# Power-Sheet-1.net
KiCad netlist of a schematic drawn in Altium Designer
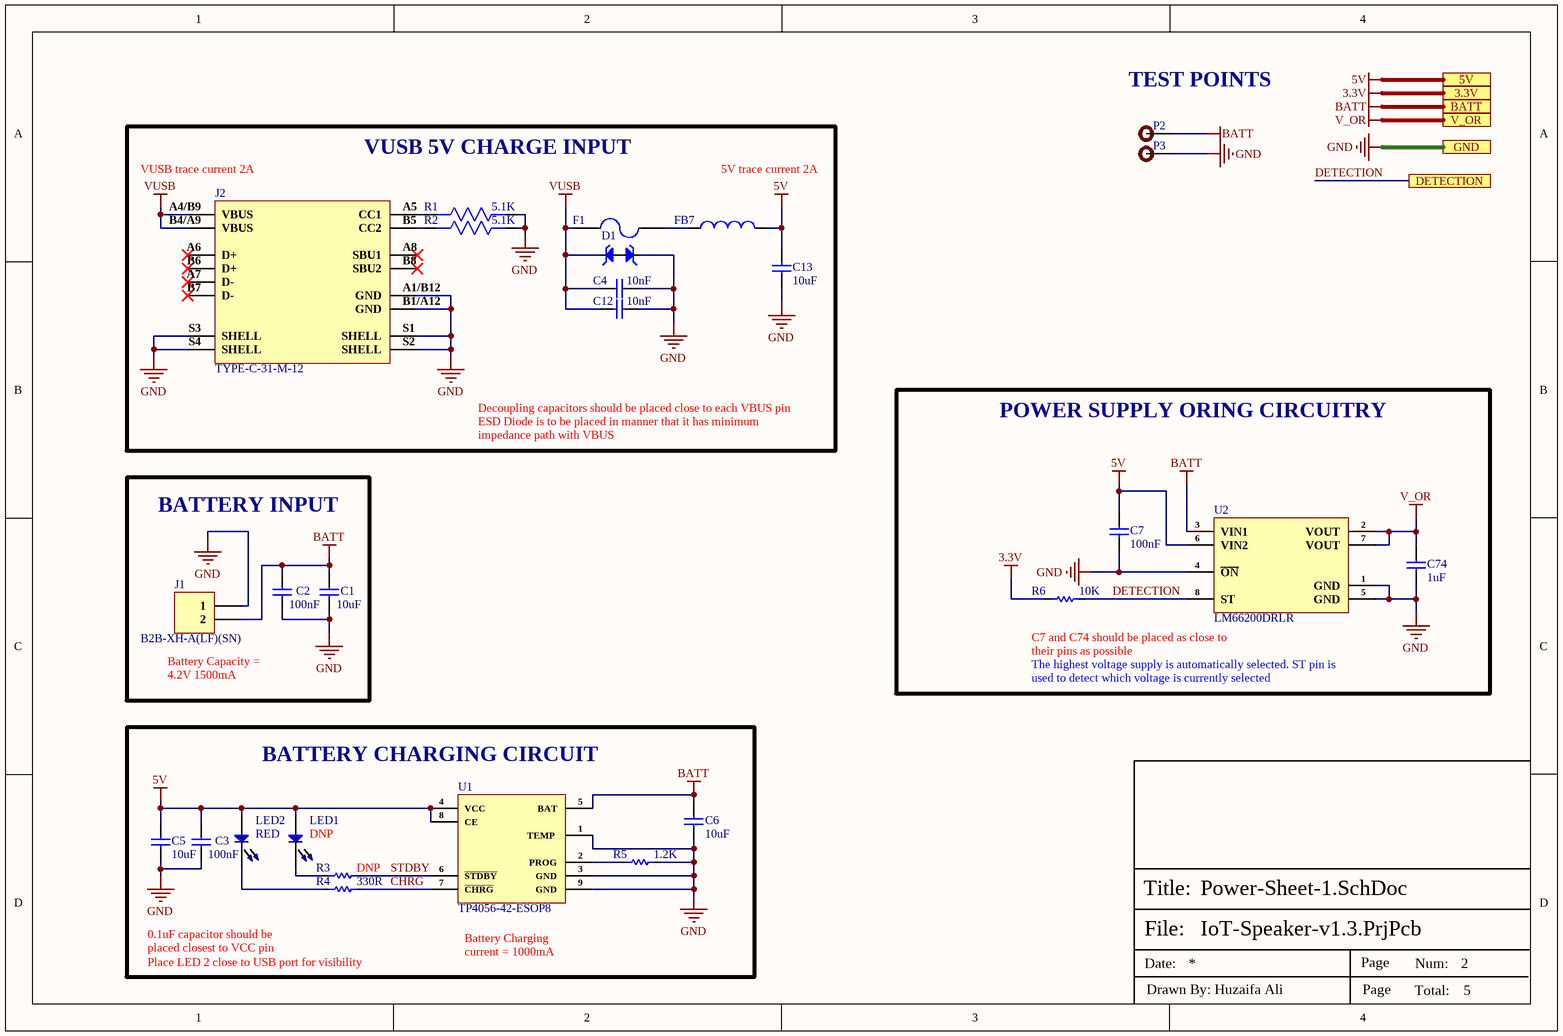
[diagram p0: Power-Sheet-1.SchDoc]

(export (version "E")
  (design (tool "Eeschema 10.0.6"))
  (components
    (comp (ref "C1")
      (value "10uF")
      (footprint "Cap-0805")
      (description "CAP CER 10UF 25V X5R 0805")
      (fields
        (field (name "MANUFACTURER") "Yageo")
        (field (name "MANUFACTURER PART NUMBER") "CC0805KKX5R8BB106")
      )
      (libsource (lib "eSpark_centralized_Library(2022)") (part "CC0805KKX5R8BB106"))
    )
    (comp (ref "C2")
      (value "100nF")
      (footprint "Cap-0402")
      (description "CAP CER 0.1UF 25V X5R 0402")
      (fields
        (field (name "MANUFACTURER") "Yageo")
        (field (name "MANUFACTURER PART NUMBER") "CC0402KRX5R8BB104")
      )
      (libsource (lib "eSpark_centralized_Library(2022)") (part "CC0402KRX5R8BB104"))
    )
    (comp (ref "C3")
      (value "100nF")
      (footprint "Cap-0402")
      (description "CAP CER 0.1UF 25V X5R 0402")
      (fields
        (field (name "MANUFACTURER") "Yageo")
        (field (name "MANUFACTURER PART NUMBER") "CC0402KRX5R8BB104")
      )
      (libsource (lib "eSpark_centralized_Library(2022)") (part "CC0402KRX5R8BB104"))
    )
    (comp (ref "C4")
      (value "10nF")
      (footprint "Cap-0603")
      (description "CAP CER 10000PF 50V C0G/NPO 0603")
      (fields
        (field (name "MANUFACTURER") "Yageo")
        (field (name "MANUFACTURER PART NUMBER") "CC0603JRNPO9BN103")
      )
      (libsource (lib "eSpark_centralized_Library(2022)") (part "CC0603JRNPO9BN103"))
    )
    (comp (ref "C5")
      (value "10uF")
      (footprint "Cap-0805")
      (description "CAP CER 10UF 25V X5R 0805")
      (fields
        (field (name "MANUFACTURER") "Yageo")
        (field (name "MANUFACTURER PART NUMBER") "CC0805KKX5R8BB106")
      )
      (libsource (lib "eSpark_centralized_Library(2022)") (part "CC0805KKX5R8BB106"))
    )
    (comp (ref "C6")
      (value "10uF")
      (footprint "Cap-0805")
      (description "CAP CER 10UF 25V X5R 0805")
      (fields
        (field (name "MANUFACTURER") "Yageo")
        (field (name "MANUFACTURER PART NUMBER") "CC0805KKX5R8BB106")
      )
      (libsource (lib "eSpark_centralized_Library(2022)") (part "CC0805KKX5R8BB106"))
    )
    (comp (ref "C7")
      (value "100nF")
      (footprint "Cap-0402")
      (description "CAP CER 0.1UF 25V X5R 0402")
      (fields
        (field (name "MANUFACTURER") "Yageo")
        (field (name "MANUFACTURER PART NUMBER") "CC0402KRX5R8BB104")
      )
      (libsource (lib "eSpark_centralized_Library(2022)") (part "CC0402KRX5R8BB104"))
    )
    (comp (ref "C12")
      (value "10nF")
      (footprint "Cap-0603")
      (description "CAP CER 10000PF 50V C0G/NPO 0603")
      (fields
        (field (name "MANUFACTURER") "Yageo")
        (field (name "MANUFACTURER PART NUMBER") "CC0603JRNPO9BN103")
      )
      (libsource (lib "eSpark_centralized_Library(2022)") (part "CC0603JRNPO9BN103"))
    )
    (comp (ref "C13")
      (value "10uF")
      (footprint "Cap-0805")
      (description "CAP CER 10UF 25V X5R 0805")
      (fields
        (field (name "MANUFACTURER") "Yageo")
        (field (name "MANUFACTURER PART NUMBER") "CC0805KKX5R8BB106")
      )
      (libsource (lib "eSpark_centralized_Library(2022)") (part "CC0805KKX5R8BB106"))
    )
    (comp (ref "C74")
      (value "1uF")
      (footprint "Cap-0603")
      (description "CAP CER 1UF 25V X5R 0603")
      (fields
        (field (name "MANUFACTURER") "Yageo")
        (field (name "MANUFACTURER PART NUMBER") "CC0603KRX5R8BB105")
      )
      (libsource (lib "eSpark_centralized_Library(2022)") (part "CC0603KRX5R8BB105"))
    )
    (comp (ref "D1")
      (value "PESD5V0H1BSFYL")
      (footprint "DSN0603-2")
      (description "TVS DIODE 5VWM 6.3VC DSN0603-2")
      (fields (field (name "MANUFACTURER") "Nexperia") (field (name "LCSC PART NUMBER") "C477989"))
      (libsource (lib "eSpark Libraries") (part "PESD5V0H1BSFYL"))
    )
    (comp (ref "F1")
      (value "BSMD0805L-200")
      (footprint "Fuse-0805")
      (description "6V 2A 50A 1W -40℃~+85℃ 4A 4mΩ 5s 45mΩ 0805 Resettable Fuses ROHS")
      (fields (field (name "MANUFACTURER") "BHFUSE") (field (name "LCSC PART NUMBER") "C2757931"))
      (libsource (lib "eSpark_centralized_Library(2022)") (part "BSMD0805L-200"))
    )
    (comp (ref "FB7")
      (value "100MHz")
      (footprint "IND-1206")
      (description "FERRITE BEAD 120 OHM 1206 1LN")
      (fields
        (field (name "MANUFACTURER") "Murata")
        (field (name "MANUFACTURER PART NUMBER") "BLM31PG121SN1L")
      )
      (libsource (lib "eSpark_centralized_Library(2022)") (part "BLM31PG121SN1L"))
    )
    (comp (ref "J1")
      (value "B2B-XH-A(LF)(SN)")
      (footprint "B2B-XH-A(LF)(SN)_")
      (description "Conn Shrouded Header (4 Sides) HDR 2 POS 2.5mm Solder ST Thru-Hole Box")
      (fields (field (name "MANUFACTURER") "JST") (field (name "LCSC PART NUMBER") "C158012"))
      (libsource (lib "eSpark_centralized_Library(2022)") (part "B2B-XH-A(LF)(SN)"))
    )
    (comp (ref "J2")
      (value "TYPE-C-31-M-12")
      (footprint "TYPE-C-31-M-12_")
      (description "250mA 1 16 Female Type-C SMD USB Connectors ROHS")
      (fields
        (field (name "MANUFACTURER") "Korean Hroparts Elec")
        (field (name "LCSC PART NUMBER") "C165948")
      )
      (libsource (lib "eSpark_centralized_Library(2022)") (part "TYPE-C-31-M-12"))
    )
    (comp (ref "LED1")
      (value "DNP")
      (footprint "LED-0603")
      (description "Emerald 0603 Light Emitting Diodes (LED) ROHS")
      (fields
        (field (name "MANUFACTURER") "Foshan NationStar Optoelectronics")
        (field (name "MANUFACTURER PART NUMBER") "NCD0603G2")
      )
      (libsource (lib "eSpark_centralized_Library(2022)") (part "NCD0603G2"))
    )
    (comp (ref "LED2")
      (value "RED")
      (footprint "LED-0603")
      (description "0603 Light Emitting Diodes (LED) ROHS")
      (fields
        (field (name "MANUFACTURER") "Foshan NationStar Optoelectronics")
        (field (name "MANUFACTURER PART NUMBER") "NCD0603R3")
      )
      (libsource (lib "eSpark_centralized_Library(2022)") (part "NCD0603R3"))
    )
    (comp (ref "P2")
      (value "TEST POINT")
      (footprint "Test-point")
      (description "Test Point ON")
      (libsource (lib "eSpark_centralized_Library(2022)") (part "TEST POINT"))
    )
    (comp (ref "P3")
      (value "TEST POINT")
      (footprint "Test-point")
      (description "Test Point ON")
      (libsource (lib "eSpark_centralized_Library(2022)") (part "TEST POINT"))
    )
    (comp (ref "R1")
      (value "5.1K")
      (footprint "Res-0603")
      (description "RES 5.1K OHM 1% 1/10W 0603")
      (fields
        (field (name "MANUFACTURER") "Yageo")
        (field (name "MANUFACTURER PART NUMBER") "RC0603FR-075K1L")
      )
      (libsource (lib "eSpark_centralized_Library(2022)") (part "RC0603FR-075K1L"))
    )
    (comp (ref "R2")
      (value "5.1K")
      (footprint "Res-0603")
      (description "RES 5.1K OHM 1% 1/10W 0603")
      (fields
        (field (name "MANUFACTURER") "Yageo")
        (field (name "MANUFACTURER PART NUMBER") "RC0603FR-075K1L")
      )
      (libsource (lib "eSpark_centralized_Library(2022)") (part "RC0603FR-075K1L"))
    )
    (comp (ref "R3")
      (value "DNP")
      (footprint "Res-0603")
      (description "RES SMD 220 OHM 1% 1/10W 0603")
      (fields
        (field (name "MANUFACTURER") "Yageo")
        (field (name "MANUFACTURER PART NUMBER") "RC0603FR-07220RL")
      )
      (libsource (lib "eSpark_centralized_Library(2022)") (part "RC0603FR-07220RL"))
    )
    (comp (ref "R4")
      (value "330R")
      (footprint "Res-0603")
      (description "RES  SMD 330R 100 mW 0603")
      (fields
        (field (name "MANUFACTURER") "Yageo")
        (field (name "MANUFACTURER PART NUMBER") "RC0603JR-07330RL")
      )
      (libsource (lib "eSpark_centralized_Library(2022)") (part "RC0603JR-07330RL"))
    )
    (comp (ref "R5")
      (value "1.2K")
      (footprint "Res-0603")
      (description "Thick Film Resistors 75V 1.2kΩ 0603 Chip Resistor - Surface Mount ROHS")
      (fields
        (field (name "MANUFACTURER") "UNI-ROYAL")
        (field (name "MANUFACTURER PART NUMBER") "0603WAF1201T5E")
      )
      (libsource (lib "eSpark_centralized_Library(2022)") (part "0603WAF1201T5E"))
    )
    (comp (ref "R6")
      (value "10K")
      (footprint "Res-0603")
      (description "RES SMD 10K Ohm 1% 1/10W 0603")
      (fields
        (field (name "MANUFACTURER") "Yageo")
        (field (name "MANUFACTURER PART NUMBER") "RC0603FR-0710KL")
      )
      (libsource (lib "eSpark_centralized_Library(2022)") (part "RC0603FR-0710KL"))
    )
    (comp (ref "U1")
      (value "TP4056-42-ESOP8")
      (footprint "ESOP-8")
      (description "ESOP-8 Battery Management ICs ROHS")
      (fields (field (name "MANUFACTURER") "TOPPOWER") (field (name "LCSC PART NUMBER") "C16581"))
      (libsource (lib "eSpark_centralized_Library(2022)") (part "TP4056-42-ESOP8"))
    )
    (comp (ref "U2")
      (value "LM66200DRLR")
      (footprint "SOT-583")
      (description "OR Controller N+1 ORing Controller N-Channel 2:1 SOT-583")
      (fields (field (name "MANUFACTURER") "Texas Instruments") (field (name "LCSC PART NUMBER") "C3235556"))
      (libsource (lib "eSpark_centralized_Library(2022)") (part "LM66200DRLR"))
    )
  )
  (nets
    (net (code "1") (name "/CHRG") (class "Default")
      (node (ref "R4") (pin "2") (pinfunction "2_2") (pintype "passive"))
      (node (ref "U1") (pin "7") (pinfunction "~{CHRG}_7") (pintype "passive"))
    )
    (net (code "2") (name "/DETECTION") (class "Default")
      (node (ref "R6") (pin "2") (pinfunction "2_2") (pintype "passive"))
      (node (ref "U2") (pin "8") (pinfunction "ST_8") (pintype "passive"))
    )
    (net (code "3") (name "/STDBY") (class "Default")
      (node (ref "R3") (pin "2") (pinfunction "2_2") (pintype "passive"))
      (node (ref "U1") (pin "6") (pinfunction "~{STDBY}_6") (pintype "passive"))
    )
    (net (code "4") (name "3.3V") (class "Default")
      (node (ref "R6") (pin "1") (pinfunction "1_1") (pintype "passive"))
    )
    (net (code "5") (name "5V") (class "Default")
      (node (ref "C13") (pin "2") (pinfunction "2_2") (pintype "passive"))
      (node (ref "C3") (pin "2") (pinfunction "2_2") (pintype "passive"))
      (node (ref "C5") (pin "2") (pinfunction "2_2") (pintype "passive"))
      (node (ref "C7") (pin "2") (pinfunction "2_2") (pintype "passive"))
      (node (ref "FB7") (pin "2") (pinfunction "2_2") (pintype "passive"))
      (node (ref "LED1") (pin "1") (pinfunction "1_1") (pintype "passive"))
      (node (ref "LED2") (pin "1") (pinfunction "1_1") (pintype "passive"))
      (node (ref "U1") (pin "4") (pinfunction "VCC_4") (pintype "passive"))
      (node (ref "U1") (pin "8") (pinfunction "CE_8") (pintype "passive"))
      (node (ref "U2") (pin "6") (pinfunction "VIN2_6") (pintype "passive"))
    )
    (net (code "6") (name "BATT") (class "Default")
      (node (ref "C1") (pin "2") (pinfunction "2_2") (pintype "passive"))
      (node (ref "C2") (pin "2") (pinfunction "2_2") (pintype "passive"))
      (node (ref "C6") (pin "2") (pinfunction "2_2") (pintype "passive"))
      (node (ref "J1") (pin "2") (pinfunction "2_2") (pintype "passive"))
      (node (ref "P2") (pin "1") (pinfunction "1_1") (pintype "passive"))
      (node (ref "U1") (pin "5") (pinfunction "BAT_5") (pintype "passive"))
      (node (ref "U2") (pin "3") (pinfunction "VIN1_3") (pintype "passive"))
    )
    (net (code "7") (name "GND") (class "Default")
      (node (ref "C1") (pin "1") (pinfunction "1_1") (pintype "passive"))
      (node (ref "C12") (pin "2") (pinfunction "2_2") (pintype "passive"))
      (node (ref "C13") (pin "1") (pinfunction "1_1") (pintype "passive"))
      (node (ref "C2") (pin "1") (pinfunction "1_1") (pintype "passive"))
      (node (ref "C3") (pin "1") (pinfunction "1_1") (pintype "passive"))
      (node (ref "C4") (pin "2") (pinfunction "2_2") (pintype "passive"))
      (node (ref "C5") (pin "1") (pinfunction "1_1") (pintype "passive"))
      (node (ref "C6") (pin "1") (pinfunction "1_1") (pintype "passive"))
      (node (ref "C7") (pin "1") (pinfunction "1_1") (pintype "passive"))
      (node (ref "C74") (pin "1") (pinfunction "1_1") (pintype "passive"))
      (node (ref "D1") (pin "2") (pinfunction "2_2") (pintype "passive"))
      (node (ref "J1") (pin "1") (pinfunction "1_1") (pintype "passive"))
      (node (ref "J2") (pin "A1/B12") (pinfunction "GND_A1/B12") (pintype "power_in"))
      (node (ref "J2") (pin "B1/A12") (pinfunction "GND_B1/A12") (pintype "power_in"))
      (node (ref "J2") (pin "S1") (pinfunction "SHELL_S1") (pintype "passive"))
      (node (ref "J2") (pin "S2") (pinfunction "SHELL_S2") (pintype "passive"))
      (node (ref "J2") (pin "S3") (pinfunction "SHELL_S3") (pintype "passive"))
      (node (ref "J2") (pin "S4") (pinfunction "SHELL_S4") (pintype "passive"))
      (node (ref "P3") (pin "1") (pinfunction "1_1") (pintype "passive"))
      (node (ref "R1") (pin "1") (pintype "passive"))
      (node (ref "R2") (pin "1") (pintype "passive"))
      (node (ref "R5") (pin "1") (pinfunction "1_1") (pintype "passive"))
      (node (ref "U1") (pin "1") (pinfunction "TEMP_1") (pintype "passive"))
      (node (ref "U1") (pin "3") (pinfunction "GND_3") (pintype "passive"))
      (node (ref "U1") (pin "9") (pinfunction "GND_9") (pintype "passive"))
      (node (ref "U2") (pin "1") (pinfunction "GND_1") (pintype "passive"))
      (node (ref "U2") (pin "4") (pinfunction "~{ON}_4") (pintype "passive"))
      (node (ref "U2") (pin "5") (pinfunction "GND_5") (pintype "passive"))
    )
    (net (code "8") (name "Net-(F1-Pad2)") (class "Default")
      (node (ref "F1") (pin "2") (pinfunction "2_2") (pintype "passive"))
      (node (ref "FB7") (pin "1") (pinfunction "1_1") (pintype "passive"))
    )
    (net (code "9") (name "Net-(J2-CC1)") (class "Default")
      (node (ref "J2") (pin "A5") (pinfunction "CC1_A5") (pintype "passive"))
      (node (ref "R1") (pin "2") (pintype "passive"))
    )
    (net (code "10") (name "Net-(J2-CC2)") (class "Default")
      (node (ref "J2") (pin "B5") (pinfunction "CC2_B5") (pintype "passive"))
      (node (ref "R2") (pin "2") (pintype "passive"))
    )
    (net (code "11") (name "Net-(LED1-Pad2)") (class "Default")
      (node (ref "LED1") (pin "2") (pinfunction "2_2") (pintype "passive"))
      (node (ref "R3") (pin "1") (pinfunction "1_1") (pintype "passive"))
    )
    (net (code "12") (name "Net-(LED2-Pad2)") (class "Default")
      (node (ref "LED2") (pin "2") (pinfunction "2_2") (pintype "passive"))
      (node (ref "R4") (pin "1") (pinfunction "1_1") (pintype "passive"))
    )
    (net (code "13") (name "Net-(U1-PROG)") (class "Default")
      (node (ref "R5") (pin "2") (pinfunction "2_2") (pintype "passive"))
      (node (ref "U1") (pin "2") (pinfunction "PROG_2") (pintype "passive"))
    )
    (net (code "14") (name "VUSB") (class "Default")
      (node (ref "C12") (pin "1") (pinfunction "1_1") (pintype "passive"))
      (node (ref "C4") (pin "1") (pinfunction "1_1") (pintype "passive"))
      (node (ref "D1") (pin "1") (pinfunction "1_1") (pintype "passive"))
      (node (ref "F1") (pin "1") (pinfunction "1_1") (pintype "passive"))
      (node (ref "J2") (pin "A4/B9") (pinfunction "VBUS_A4/B9") (pintype "power_in"))
      (node (ref "J2") (pin "B4/A9") (pinfunction "VBUS_B4/A9") (pintype "power_in"))
    )
    (net (code "15") (name "V_OR") (class "Default")
      (node (ref "C74") (pin "2") (pinfunction "2_2") (pintype "passive"))
      (node (ref "U2") (pin "2") (pinfunction "VOUT_2") (pintype "passive"))
      (node (ref "U2") (pin "7") (pinfunction "VOUT_7") (pintype "passive"))
    )
    (net (code "16") (name "unconnected-(J2-D+-PadA6)") (class "Default")
      (node (ref "J2") (pin "A6") (pinfunction "D+_A6") (pintype "passive+no_connect"))
    )
    (net (code "17") (name "unconnected-(J2-D+-PadB6)") (class "Default")
      (node (ref "J2") (pin "B6") (pinfunction "D+_B6") (pintype "passive+no_connect"))
    )
    (net (code "18") (name "unconnected-(J2-D--PadA7)") (class "Default")
      (node (ref "J2") (pin "A7") (pinfunction "D-_A7") (pintype "passive+no_connect"))
    )
    (net (code "19") (name "unconnected-(J2-D--PadB7)") (class "Default")
      (node (ref "J2") (pin "B7") (pinfunction "D-_B7") (pintype "passive+no_connect"))
    )
    (net (code "20") (name "unconnected-(J2-SBU1-PadA8)") (class "Default")
      (node (ref "J2") (pin "A8") (pinfunction "SBU1_A8") (pintype "passive+no_connect"))
    )
    (net (code "21") (name "unconnected-(J2-SBU2-PadB8)") (class "Default")
      (node (ref "J2") (pin "B8") (pinfunction "SBU2_B8") (pintype "passive+no_connect"))
    )
  )
)
